# FTDI_Basic_5V-v12.net
KiCad netlist of a schematic drawn in EAGLE
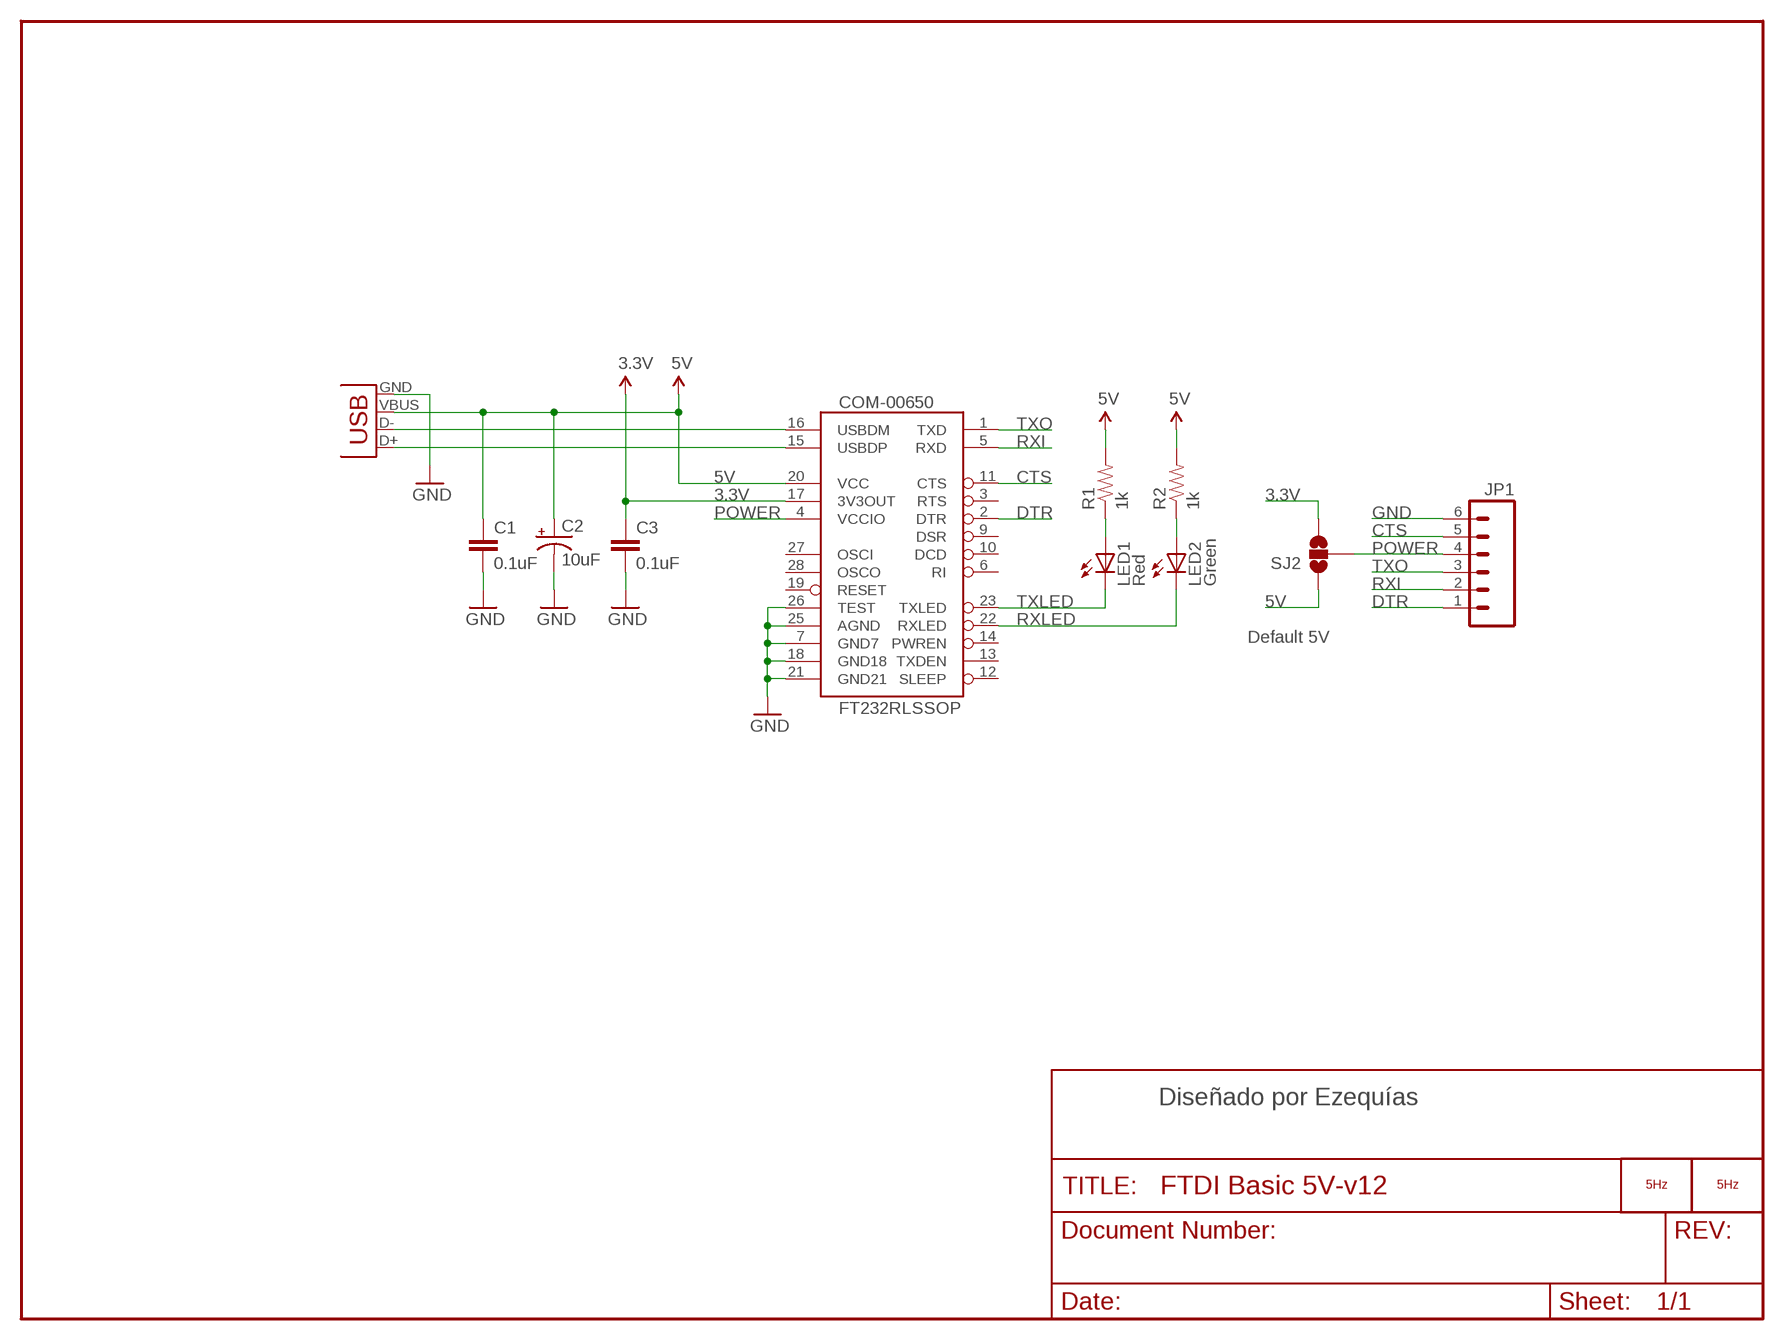
[diagram p0: schematic, sheet 1]

(export (version "E")
  (design (tool "Eeschema 10.0.6"))
  (components
    (comp (ref "C1")
      (value "0.1uF")
      (footprint "eagle-import:0603-CAP")
      (libsource (lib "eagle-import") (part "CAP0603-CAP"))
    )
    (comp (ref "C2")
      (value "10uF")
      (footprint "eagle-import:EIA3216")
      (libsource (lib "eagle-import") (part "CAP_POL1206"))
    )
    (comp (ref "C3")
      (value "0.1uF")
      (footprint "eagle-import:0603-CAP")
      (libsource (lib "eagle-import") (part "CAP0603-CAP"))
    )
    (comp (ref "COM-00650")
      (value "FT232RLSSOP")
      (footprint "eagle-import:SSOP28DB")
      (libsource (lib "eagle-import") (part "FT232RLSSOP"))
    )
    (comp (ref "JP1")
      (value "M06SIP")
      (footprint "eagle-import:1X06")
      (libsource (lib "eagle-import") (part "M06SIP"))
    )
    (comp (ref "LED1")
      (value "Red")
      (footprint "eagle-import:LED-0603")
      (libsource (lib "eagle-import") (part "LED0603"))
    )
    (comp (ref "LED2")
      (value "Green")
      (footprint "eagle-import:LED-0603")
      (libsource (lib "eagle-import") (part "LED0603"))
    )
    (comp (ref "LOGO1")
      (value "LOGO_5HZ_H_5MM")
      (footprint "eagle-import:5HZ_LOGO_H_5MM")
      (libsource (lib "eagle-import") (part "LOGO_5HZ_H_5MM"))
    )
    (comp (ref "LOGO2")
      (value "LOGO_5HZ_H_15MM")
      (footprint "eagle-import:5HZ_LOGO_H_15MM")
      (libsource (lib "eagle-import") (part "LOGO_5HZ_H_15MM"))
    )
    (comp (ref "PRT-00587")
      (value "897-43-005-00-100001")
      (footprint "eagle-import:USB-MINIB")
      (libsource (lib "eagle-import") (part "USBSMD"))
    )
    (comp (ref "R1")
      (value "1k")
      (footprint "eagle-import:0603-RES")
      (libsource (lib "eagle-import") (part "RESISTOR0603-RES"))
    )
    (comp (ref "R2")
      (value "1k")
      (footprint "eagle-import:0603-RES")
      (libsource (lib "eagle-import") (part "RESISTOR0603-RES"))
    )
    (comp (ref "SJ2")
      (value "SOLDERJUMPER_2WAYS")
      (footprint "eagle-import:SJ_3")
      (libsource (lib "eagle-import") (part "SOLDERJUMPER_2WAYS"))
    )
  )
  (nets
    (net (code "1") (name "/CTS") (class "Default")
      (node (ref "COM-00650") (pin "11") (pinfunction "CTS_11") (pintype "input"))
      (node (ref "JP1") (pin "5") (pinfunction "5_5") (pintype "passive"))
    )
    (net (code "2") (name "/DTR") (class "Default")
      (node (ref "COM-00650") (pin "2") (pinfunction "DTR_2") (pintype "output"))
      (node (ref "JP1") (pin "1") (pinfunction "1_1") (pintype "passive"))
    )
    (net (code "3") (name "/POWER") (class "Default")
      (node (ref "COM-00650") (pin "4") (pinfunction "VCCIO_4") (pintype "power_in"))
      (node (ref "JP1") (pin "4") (pinfunction "4_4") (pintype "passive"))
      (node (ref "SJ2") (pin "2") (pinfunction "2_2") (pintype "passive"))
    )
    (net (code "4") (name "/RXI") (class "Default")
      (node (ref "COM-00650") (pin "5") (pinfunction "RXD_5") (pintype "input"))
      (node (ref "JP1") (pin "2") (pinfunction "2_2") (pintype "passive"))
    )
    (net (code "5") (name "/RXLED") (class "Default")
      (node (ref "COM-00650") (pin "22") (pinfunction "RXLED_22") (pintype "input"))
      (node (ref "LED2") (pin "C") (pinfunction "C_C") (pintype "passive"))
    )
    (net (code "6") (name "/TXLED") (class "Default")
      (node (ref "COM-00650") (pin "23") (pinfunction "TXLED_23") (pintype "input"))
      (node (ref "LED1") (pin "C") (pinfunction "C_C") (pintype "passive"))
    )
    (net (code "7") (name "/TXO") (class "Default")
      (node (ref "COM-00650") (pin "1") (pinfunction "TXD_1") (pintype "output"))
      (node (ref "JP1") (pin "3") (pinfunction "3_3") (pintype "passive"))
    )
    (net (code "8") (name "3.3V") (class "Default")
      (node (ref "C3") (pin "1") (pinfunction "1_1") (pintype "passive"))
      (node (ref "COM-00650") (pin "17") (pinfunction "3V3OUT_17") (pintype "output"))
      (node (ref "SJ2") (pin "3") (pinfunction "3_3") (pintype "passive"))
    )
    (net (code "9") (name "5V") (class "Default")
      (node (ref "C1") (pin "1") (pinfunction "1_1") (pintype "passive"))
      (node (ref "C2") (pin "A") (pinfunction "+_A") (pintype "passive"))
      (node (ref "COM-00650") (pin "20") (pinfunction "VCC_20") (pintype "power_in"))
      (node (ref "PRT-00587") (pin "VBUS") (pinfunction "VBUS_VBUS") (pintype "bidirectional"))
      (node (ref "R1") (pin "2") (pinfunction "2_2") (pintype "passive"))
      (node (ref "R2") (pin "2") (pinfunction "2_2") (pintype "passive"))
      (node (ref "SJ2") (pin "1") (pinfunction "1_1") (pintype "passive"))
    )
    (net (code "10") (name "GND") (class "Default")
      (node (ref "C1") (pin "2") (pinfunction "2_2") (pintype "passive"))
      (node (ref "C2") (pin "C") (pinfunction "-_C") (pintype "passive"))
      (node (ref "C3") (pin "2") (pinfunction "2_2") (pintype "passive"))
      (node (ref "COM-00650") (pin "18") (pinfunction "GND18_18") (pintype "power_in"))
      (node (ref "COM-00650") (pin "21") (pinfunction "GND21_21") (pintype "power_in"))
      (node (ref "COM-00650") (pin "25") (pinfunction "AGND_25") (pintype "power_in"))
      (node (ref "COM-00650") (pin "26") (pinfunction "TEST_26") (pintype "input"))
      (node (ref "COM-00650") (pin "7") (pinfunction "GND7_7") (pintype "power_in"))
      (node (ref "JP1") (pin "6") (pinfunction "6_6") (pintype "passive"))
      (node (ref "PRT-00587") (pin "GND") (pinfunction "GND_GND") (pintype "bidirectional"))
    )
    (net (code "11") (name "Net-(COM-00650-USBDM)") (class "Default")
      (node (ref "COM-00650") (pin "16") (pinfunction "USBDM_16") (pintype "bidirectional"))
      (node (ref "PRT-00587") (pin "D-") (pinfunction "D-_D-") (pintype "bidirectional"))
    )
    (net (code "12") (name "Net-(COM-00650-USBDP)") (class "Default")
      (node (ref "COM-00650") (pin "15") (pinfunction "USBDP_15") (pintype "bidirectional"))
      (node (ref "PRT-00587") (pin "D+") (pinfunction "D+_D+") (pintype "bidirectional"))
    )
    (net (code "13") (name "Net-(LED1-PadA)") (class "Default")
      (node (ref "LED1") (pin "A") (pinfunction "A_A") (pintype "passive"))
      (node (ref "R1") (pin "1") (pinfunction "1_1") (pintype "passive"))
    )
    (net (code "14") (name "Net-(LED2-PadA)") (class "Default")
      (node (ref "LED2") (pin "A") (pinfunction "A_A") (pintype "passive"))
      (node (ref "R2") (pin "1") (pinfunction "1_1") (pintype "passive"))
    )
    (net (code "15") (name "unconnected-(COM-00650-DCD-Pad10)") (class "Default")
      (node (ref "COM-00650") (pin "10") (pinfunction "DCD_10") (pintype "input"))
    )
    (net (code "16") (name "unconnected-(COM-00650-DSR-Pad9)") (class "Default")
      (node (ref "COM-00650") (pin "9") (pinfunction "DSR_9") (pintype "input"))
    )
    (net (code "17") (name "unconnected-(COM-00650-OSCI-Pad27)") (class "Default")
      (node (ref "COM-00650") (pin "27") (pinfunction "OSCI_27") (pintype "input"))
    )
    (net (code "18") (name "unconnected-(COM-00650-OSCO-Pad28)") (class "Default")
      (node (ref "COM-00650") (pin "28") (pinfunction "OSCO_28") (pintype "output"))
    )
    (net (code "19") (name "unconnected-(COM-00650-PWREN-Pad14)") (class "Default")
      (node (ref "COM-00650") (pin "14") (pinfunction "PWREN_14") (pintype "input"))
    )
    (net (code "20") (name "unconnected-(COM-00650-RESET-Pad19)") (class "Default")
      (node (ref "COM-00650") (pin "19") (pinfunction "RESET_19") (pintype "input"))
    )
    (net (code "21") (name "unconnected-(COM-00650-RI-Pad6)") (class "Default")
      (node (ref "COM-00650") (pin "6") (pinfunction "RI_6") (pintype "input"))
    )
    (net (code "22") (name "unconnected-(COM-00650-RTS-Pad3)") (class "Default")
      (node (ref "COM-00650") (pin "3") (pinfunction "RTS_3") (pintype "output"))
    )
    (net (code "23") (name "unconnected-(COM-00650-SLEEP-Pad12)") (class "Default")
      (node (ref "COM-00650") (pin "12") (pinfunction "SLEEP_12") (pintype "input"))
    )
    (net (code "24") (name "unconnected-(COM-00650-TXDEN-Pad13)") (class "Default")
      (node (ref "COM-00650") (pin "13") (pinfunction "TXDEN_13") (pintype "input"))
    )
  )
)
